# atmega2560.net
KiCad netlist of a schematic drawn in EAGLE
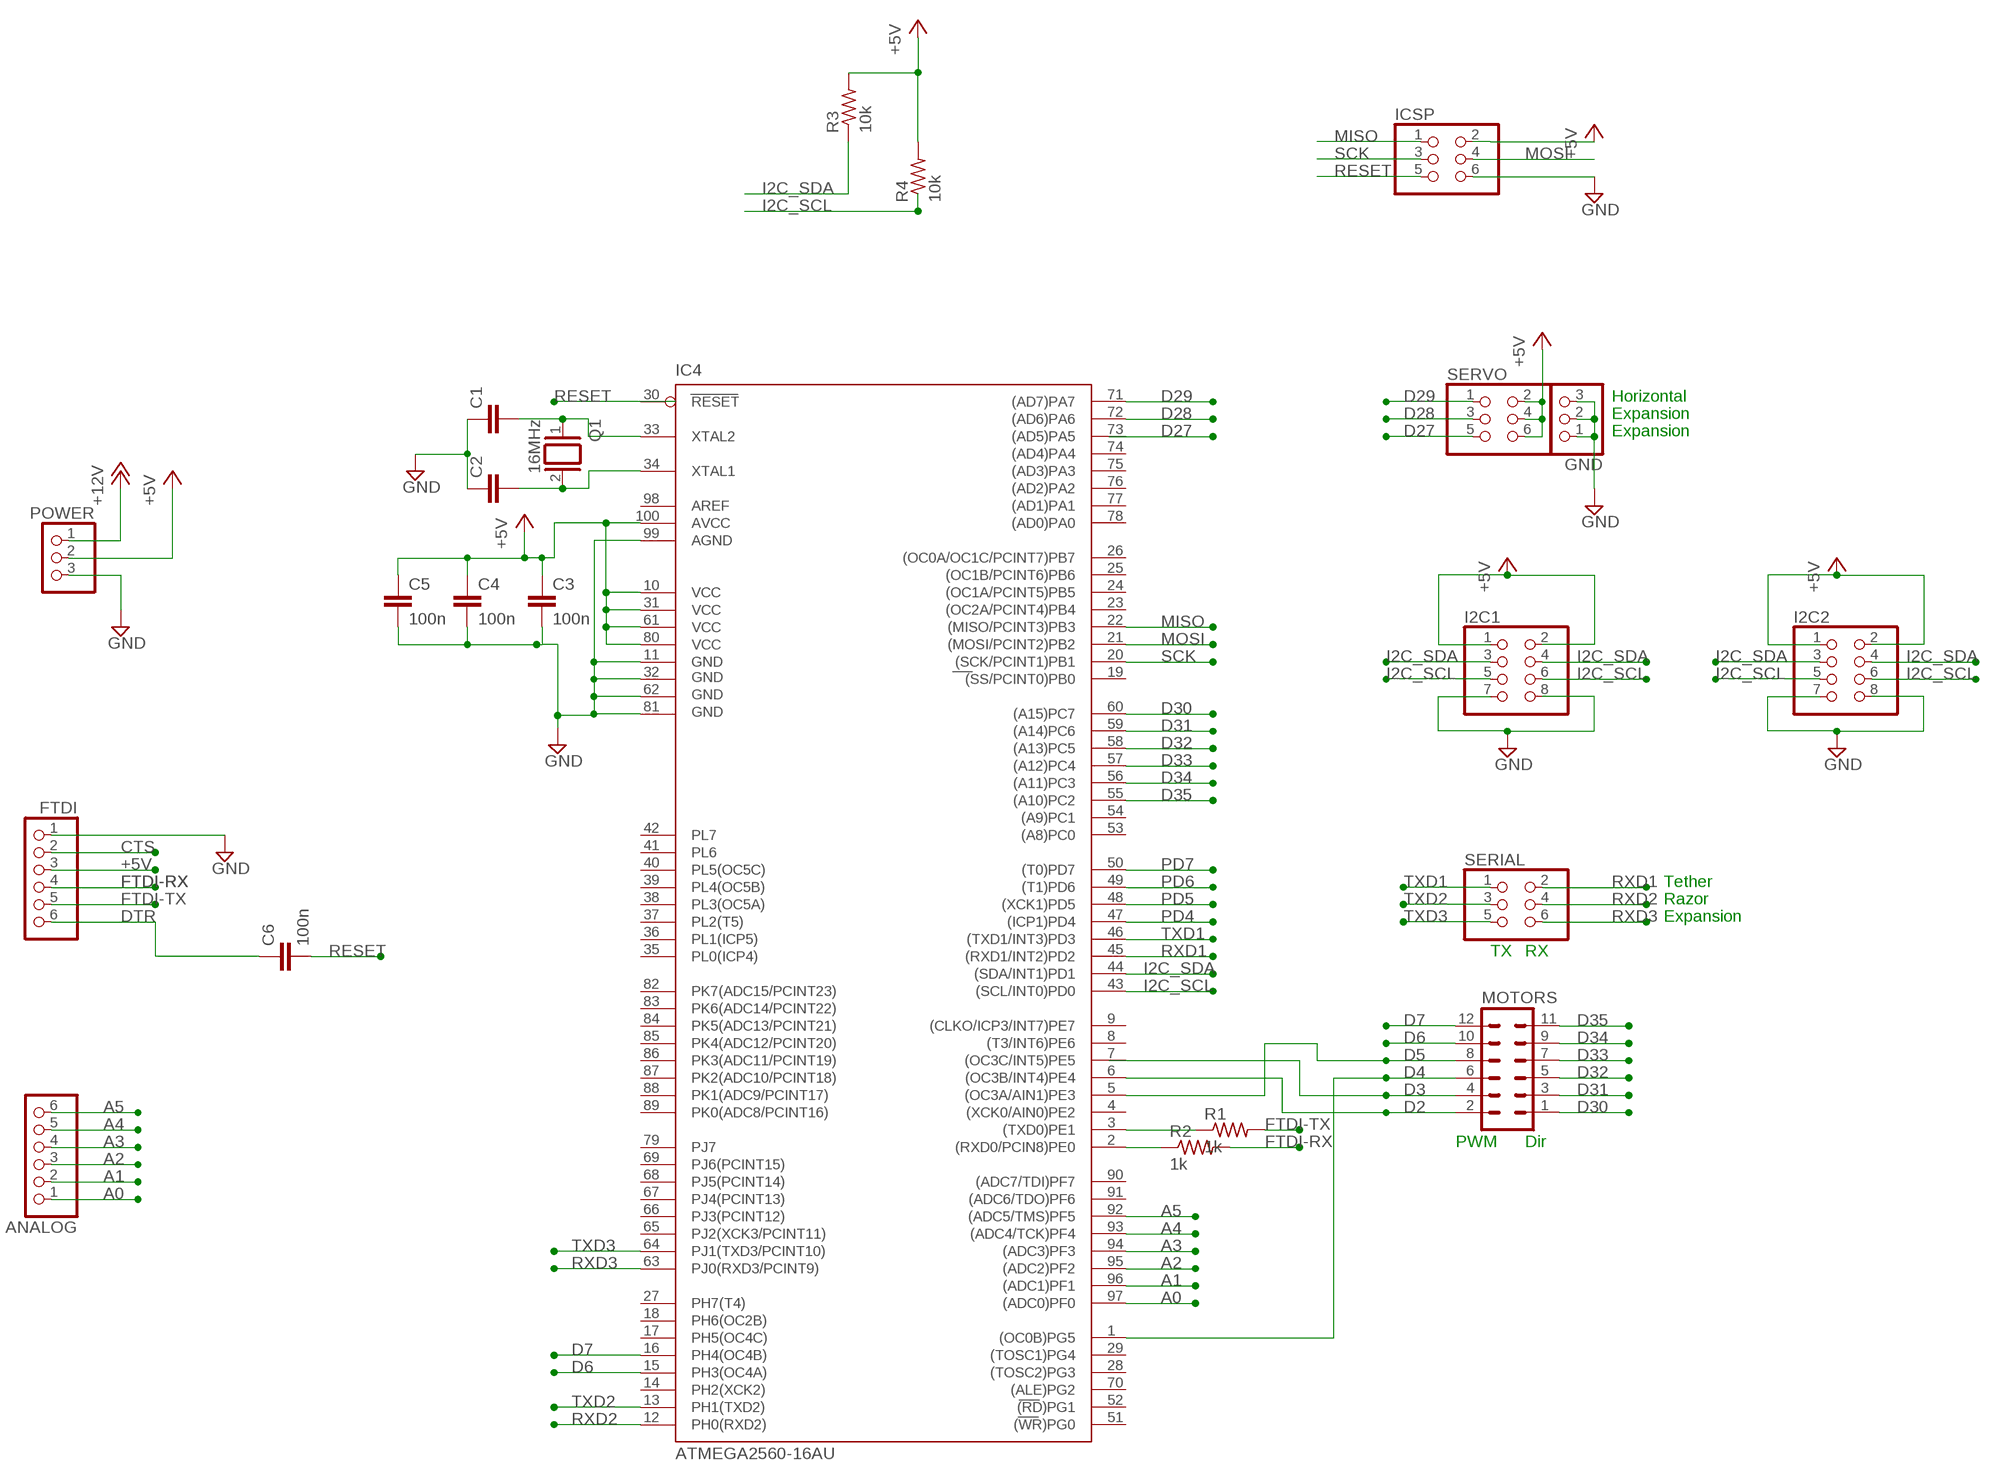
[diagram p0: schematic, sheet 1]

(export (version "E")
  (design (tool "Eeschema 10.0.6"))
  (components
    (comp (ref "ANALOG")
      (value "PINHD-1X6")
      (footprint "eagle-import:1X06")
      (libsource (lib "eagle-import") (part "PINHD-1X6"))
    )
    (comp (ref "C1")
      (value "C5/3.5")
      (footprint "eagle-import:C5B3.5")
      (libsource (lib "eagle-import") (part "C5/3.5"))
    )
    (comp (ref "C2")
      (value "C5/3.5")
      (footprint "eagle-import:C5B3.5")
      (libsource (lib "eagle-import") (part "C5/3.5"))
    )
    (comp (ref "C3")
      (value "100n")
      (footprint "eagle-import:C5B3.5")
      (libsource (lib "eagle-import") (part "C5/3.5"))
    )
    (comp (ref "C4")
      (value "100n")
      (footprint "eagle-import:C5B3.5")
      (libsource (lib "eagle-import") (part "C5/3.5"))
    )
    (comp (ref "C5")
      (value "100n")
      (footprint "eagle-import:C5B3.5")
      (libsource (lib "eagle-import") (part "C5/3.5"))
    )
    (comp (ref "C6")
      (value "100n")
      (footprint "eagle-import:C050-030X075")
      (libsource (lib "eagle-import") (part "C-EU050-030X075"))
    )
    (comp (ref "FTDI")
      (value "PINHD-1X6")
      (footprint "eagle-import:1X06")
      (libsource (lib "eagle-import") (part "PINHD-1X6"))
    )
    (comp (ref "GND")
      (value "PINHD-1X3")
      (footprint "eagle-import:1X03")
      (libsource (lib "eagle-import") (part "PINHD-1X3"))
    )
    (comp (ref "I2C1")
      (value "PINHD-2X4")
      (footprint "eagle-import:2X04")
      (libsource (lib "eagle-import") (part "PINHD-2X4"))
    )
    (comp (ref "I2C2")
      (value "PINHD-2X4")
      (footprint "eagle-import:2X04")
      (libsource (lib "eagle-import") (part "PINHD-2X4"))
    )
    (comp (ref "IC4")
      (value "ATMEGA2560-16AU")
      (footprint "eagle-import:TQFP100")
      (libsource (lib "eagle-import") (part "ATMEGAAU2560-16"))
    )
    (comp (ref "ICSP")
      (value "PINHD-2X3")
      (footprint "eagle-import:2X03")
      (libsource (lib "eagle-import") (part "PINHD-2X3"))
    )
    (comp (ref "MOTORS")
      (value "MA06-2")
      (footprint "eagle-import:MA06-2")
      (libsource (lib "eagle-import") (part "MA06-2"))
    )
    (comp (ref "POWER")
      (value "PINHD-1X3")
      (footprint "eagle-import:1X03")
      (libsource (lib "eagle-import") (part "PINHD-1X3"))
    )
    (comp (ref "Q1")
      (value "16MHz")
      (footprint "eagle-import:QS")
      (libsource (lib "eagle-import") (part "XTAL/S"))
    )
    (comp (ref "R1")
      (value "1k")
      (footprint "eagle-import:0207_7")
      (libsource (lib "eagle-import") (part "R-US_0207/7"))
    )
    (comp (ref "R2")
      (value "1k")
      (footprint "eagle-import:0207_7")
      (libsource (lib "eagle-import") (part "R-US_0207/7"))
    )
    (comp (ref "R3")
      (value "10k")
      (footprint "eagle-import:0207_7")
      (libsource (lib "eagle-import") (part "R-US_0207/7"))
    )
    (comp (ref "R4")
      (value "10k")
      (footprint "eagle-import:0207_7")
      (libsource (lib "eagle-import") (part "R-US_0207/7"))
    )
    (comp (ref "SERIAL")
      (value "PINHD-2X3")
      (footprint "eagle-import:2X03")
      (libsource (lib "eagle-import") (part "PINHD-2X3"))
    )
    (comp (ref "SERVO")
      (value "PINHD-2X3")
      (footprint "eagle-import:2X03")
      (libsource (lib "eagle-import") (part "PINHD-2X3"))
    )
  )
  (nets
    (net (code "1") (name "+5V") (class "Default")
      (node (ref "C3") (pin "1") (pinfunction "1_1") (pintype "passive"))
      (node (ref "C4") (pin "1") (pinfunction "1_1") (pintype "passive"))
      (node (ref "C5") (pin "1") (pinfunction "1_1") (pintype "passive"))
      (node (ref "FTDI") (pin "3") (pinfunction "3_3") (pintype "passive"))
      (node (ref "I2C1") (pin "1") (pinfunction "1_1") (pintype "passive"))
      (node (ref "I2C1") (pin "2") (pinfunction "2_2") (pintype "passive"))
      (node (ref "I2C2") (pin "1") (pinfunction "1_1") (pintype "passive"))
      (node (ref "I2C2") (pin "2") (pinfunction "2_2") (pintype "passive"))
      (node (ref "IC4") (pin "10") (pinfunction "VCC_10") (pintype "power_in"))
      (node (ref "IC4") (pin "100") (pinfunction "AVCC_100") (pintype "power_in"))
      (node (ref "IC4") (pin "31") (pinfunction "VCC1_31") (pintype "power_in"))
      (node (ref "IC4") (pin "61") (pinfunction "VCC2_61") (pintype "power_in"))
      (node (ref "IC4") (pin "80") (pinfunction "VCC3_80") (pintype "power_in"))
      (node (ref "ICSP") (pin "2") (pinfunction "2_2") (pintype "passive"))
      (node (ref "POWER") (pin "2") (pinfunction "2_2") (pintype "passive"))
      (node (ref "R3") (pin "2") (pinfunction "2_2") (pintype "passive"))
      (node (ref "R4") (pin "2") (pinfunction "2_2") (pintype "passive"))
      (node (ref "SERVO") (pin "2") (pinfunction "2_2") (pintype "passive"))
      (node (ref "SERVO") (pin "4") (pinfunction "4_4") (pintype "passive"))
      (node (ref "SERVO") (pin "6") (pinfunction "6_6") (pintype "passive"))
    )
    (net (code "2") (name "+12V") (class "Default")
      (node (ref "POWER") (pin "1") (pinfunction "1_1") (pintype "passive"))
    )
    (net (code "3") (name "/A0") (class "Default")
      (node (ref "ANALOG") (pin "1") (pinfunction "1_1") (pintype "passive"))
      (node (ref "IC4") (pin "97") (pinfunction "(ADC0)PF0_97") (pintype "bidirectional"))
    )
    (net (code "4") (name "/A1") (class "Default")
      (node (ref "ANALOG") (pin "2") (pinfunction "2_2") (pintype "passive"))
      (node (ref "IC4") (pin "96") (pinfunction "(ADC1)PF1_96") (pintype "bidirectional"))
    )
    (net (code "5") (name "/A2") (class "Default")
      (node (ref "ANALOG") (pin "3") (pinfunction "3_3") (pintype "passive"))
      (node (ref "IC4") (pin "95") (pinfunction "(ADC2)PF2_95") (pintype "bidirectional"))
    )
    (net (code "6") (name "/A3") (class "Default")
      (node (ref "ANALOG") (pin "4") (pinfunction "4_4") (pintype "passive"))
      (node (ref "IC4") (pin "94") (pinfunction "(ADC3)PF3_94") (pintype "bidirectional"))
    )
    (net (code "7") (name "/A4") (class "Default")
      (node (ref "ANALOG") (pin "5") (pinfunction "5_5") (pintype "passive"))
      (node (ref "IC4") (pin "93") (pinfunction "(ADC4/TCK)PF4_93") (pintype "bidirectional"))
    )
    (net (code "8") (name "/A5") (class "Default")
      (node (ref "ANALOG") (pin "6") (pinfunction "6_6") (pintype "passive"))
      (node (ref "IC4") (pin "92") (pinfunction "(ADC5/TMS)PF5_92") (pintype "bidirectional"))
    )
    (net (code "9") (name "/CTS") (class "Default")
      (node (ref "FTDI") (pin "2") (pinfunction "2_2") (pintype "passive"))
    )
    (net (code "10") (name "/D2") (class "Default")
      (node (ref "IC4") (pin "6") (pinfunction "(OC3B/INT4)PE4_6") (pintype "bidirectional"))
      (node (ref "MOTORS") (pin "2") (pinfunction "2_2") (pintype "passive"))
    )
    (net (code "11") (name "/D3") (class "Default")
      (node (ref "MOTORS") (pin "4") (pinfunction "4_4") (pintype "passive"))
    )
    (net (code "12") (name "/D4") (class "Default")
      (node (ref "IC4") (pin "1") (pinfunction "(OC0B)PG5_1") (pintype "bidirectional"))
      (node (ref "MOTORS") (pin "6") (pinfunction "6_6") (pintype "passive"))
    )
    (net (code "13") (name "/D5") (class "Default")
      (node (ref "IC4") (pin "5") (pinfunction "(OC3A/AIN1)PE3_5") (pintype "bidirectional"))
      (node (ref "MOTORS") (pin "8") (pinfunction "8_8") (pintype "passive"))
    )
    (net (code "14") (name "/D6") (class "Default")
      (node (ref "IC4") (pin "15") (pinfunction "PH3(OC4A)_15") (pintype "bidirectional"))
      (node (ref "MOTORS") (pin "10") (pinfunction "10_10") (pintype "passive"))
    )
    (net (code "15") (name "/D7") (class "Default")
      (node (ref "IC4") (pin "16") (pinfunction "PH4(OC4B)_16") (pintype "bidirectional"))
      (node (ref "MOTORS") (pin "12") (pinfunction "12_12") (pintype "passive"))
    )
    (net (code "16") (name "/D27") (class "Default")
      (node (ref "SERVO") (pin "5") (pinfunction "5_5") (pintype "passive"))
    )
    (net (code "17") (name "/D28") (class "Default")
      (node (ref "IC4") (pin "72") (pinfunction "(AD6)PA6_72") (pintype "bidirectional"))
      (node (ref "SERVO") (pin "3") (pinfunction "3_3") (pintype "passive"))
    )
    (net (code "18") (name "/D29") (class "Default")
      (node (ref "IC4") (pin "71") (pinfunction "(AD7)PA7_71") (pintype "bidirectional"))
      (node (ref "SERVO") (pin "1") (pinfunction "1_1") (pintype "passive"))
    )
    (net (code "19") (name "/D30") (class "Default")
      (node (ref "IC4") (pin "60") (pinfunction "(A15)PC7_60") (pintype "bidirectional"))
      (node (ref "MOTORS") (pin "1") (pinfunction "1_1") (pintype "passive"))
    )
    (net (code "20") (name "/D31") (class "Default")
      (node (ref "IC4") (pin "59") (pinfunction "(A14)PC6_59") (pintype "bidirectional"))
      (node (ref "MOTORS") (pin "3") (pinfunction "3_3") (pintype "passive"))
    )
    (net (code "21") (name "/D32") (class "Default")
      (node (ref "IC4") (pin "58") (pinfunction "(A13)PC5_58") (pintype "bidirectional"))
      (node (ref "MOTORS") (pin "5") (pinfunction "5_5") (pintype "passive"))
    )
    (net (code "22") (name "/D33") (class "Default")
      (node (ref "IC4") (pin "57") (pinfunction "(A12)PC4_57") (pintype "bidirectional"))
      (node (ref "MOTORS") (pin "7") (pinfunction "7_7") (pintype "passive"))
    )
    (net (code "23") (name "/D34") (class "Default")
      (node (ref "IC4") (pin "56") (pinfunction "(A11)PC3_56") (pintype "bidirectional"))
      (node (ref "MOTORS") (pin "9") (pinfunction "9_9") (pintype "passive"))
    )
    (net (code "24") (name "/D35") (class "Default")
      (node (ref "IC4") (pin "55") (pinfunction "(A10)PC2_55") (pintype "bidirectional"))
      (node (ref "MOTORS") (pin "11") (pinfunction "11_11") (pintype "passive"))
    )
    (net (code "25") (name "/DTR") (class "Default")
      (node (ref "C6") (pin "1") (pinfunction "1_1") (pintype "passive"))
      (node (ref "FTDI") (pin "6") (pinfunction "6_6") (pintype "passive"))
    )
    (net (code "26") (name "/FTDI-RX") (class "Default")
      (node (ref "FTDI") (pin "4") (pinfunction "4_4") (pintype "passive"))
      (node (ref "R2") (pin "2") (pinfunction "2_2") (pintype "passive"))
    )
    (net (code "27") (name "/FTDI-TX") (class "Default")
      (node (ref "FTDI") (pin "5") (pinfunction "5_5") (pintype "passive"))
      (node (ref "R1") (pin "2") (pinfunction "2_2") (pintype "passive"))
    )
    (net (code "28") (name "/I2C_SCL") (class "Default")
      (node (ref "I2C1") (pin "5") (pinfunction "5_5") (pintype "passive"))
      (node (ref "I2C1") (pin "6") (pinfunction "6_6") (pintype "passive"))
      (node (ref "I2C2") (pin "5") (pinfunction "5_5") (pintype "passive"))
      (node (ref "I2C2") (pin "6") (pinfunction "6_6") (pintype "passive"))
      (node (ref "IC4") (pin "43") (pinfunction "(SCL/INT0)PD0_43") (pintype "bidirectional"))
      (node (ref "R4") (pin "1") (pinfunction "1_1") (pintype "passive"))
    )
    (net (code "29") (name "/I2C_SDA") (class "Default")
      (node (ref "I2C1") (pin "3") (pinfunction "3_3") (pintype "passive"))
      (node (ref "I2C1") (pin "4") (pinfunction "4_4") (pintype "passive"))
      (node (ref "I2C2") (pin "3") (pinfunction "3_3") (pintype "passive"))
      (node (ref "I2C2") (pin "4") (pinfunction "4_4") (pintype "passive"))
      (node (ref "IC4") (pin "44") (pinfunction "(SDA/INT1)PD1_44") (pintype "bidirectional"))
      (node (ref "R3") (pin "1") (pinfunction "1_1") (pintype "passive"))
    )
    (net (code "30") (name "/MISO") (class "Default")
      (node (ref "IC4") (pin "22") (pinfunction "(MISO/PCINT3)PB3_22") (pintype "bidirectional"))
      (node (ref "ICSP") (pin "1") (pinfunction "1_1") (pintype "passive"))
    )
    (net (code "31") (name "/MOSI") (class "Default")
      (node (ref "IC4") (pin "21") (pinfunction "(MOSI/PCINT2)PB2_21") (pintype "bidirectional"))
      (node (ref "ICSP") (pin "4") (pinfunction "4_4") (pintype "passive"))
    )
    (net (code "32") (name "/PD4") (class "Default")
      (node (ref "IC4") (pin "47") (pinfunction "(ICP1)PD4_47") (pintype "bidirectional"))
    )
    (net (code "33") (name "/PD5") (class "Default")
      (node (ref "IC4") (pin "48") (pinfunction "(XCK1)PD5_48") (pintype "bidirectional"))
    )
    (net (code "34") (name "/PD6") (class "Default")
      (node (ref "IC4") (pin "49") (pinfunction "(T1)PD6_49") (pintype "bidirectional"))
    )
    (net (code "35") (name "/PD7") (class "Default")
      (node (ref "IC4") (pin "50") (pinfunction "(T0)PD7_50") (pintype "bidirectional"))
    )
    (net (code "36") (name "/RESET") (class "Default")
      (node (ref "C6") (pin "2") (pinfunction "2_2") (pintype "passive"))
      (node (ref "ICSP") (pin "5") (pinfunction "5_5") (pintype "passive"))
    )
    (net (code "37") (name "/RXD1") (class "Default")
      (node (ref "IC4") (pin "45") (pinfunction "(RXD1/INT2)PD2_45") (pintype "bidirectional"))
      (node (ref "SERIAL") (pin "2") (pinfunction "2_2") (pintype "passive"))
    )
    (net (code "38") (name "/RXD2") (class "Default")
      (node (ref "IC4") (pin "12") (pinfunction "PH0(RXD2)_12") (pintype "bidirectional"))
      (node (ref "SERIAL") (pin "4") (pinfunction "4_4") (pintype "passive"))
    )
    (net (code "39") (name "/RXD3") (class "Default")
      (node (ref "IC4") (pin "63") (pinfunction "PJ0(RXD3/PCINT9)_63") (pintype "bidirectional"))
      (node (ref "SERIAL") (pin "6") (pinfunction "6_6") (pintype "passive"))
    )
    (net (code "40") (name "/SCK") (class "Default")
      (node (ref "IC4") (pin "20") (pinfunction "(SCK/PCINT1)PB1_20") (pintype "bidirectional"))
      (node (ref "ICSP") (pin "3") (pinfunction "3_3") (pintype "passive"))
    )
    (net (code "41") (name "/TXD1") (class "Default")
      (node (ref "IC4") (pin "46") (pinfunction "(TXD1/INT3)PD3_46") (pintype "bidirectional"))
      (node (ref "SERIAL") (pin "1") (pinfunction "1_1") (pintype "passive"))
    )
    (net (code "42") (name "/TXD2") (class "Default")
      (node (ref "IC4") (pin "13") (pinfunction "PH1(TXD2)_13") (pintype "bidirectional"))
      (node (ref "SERIAL") (pin "3") (pinfunction "3_3") (pintype "passive"))
    )
    (net (code "43") (name "/TXD3") (class "Default")
      (node (ref "IC4") (pin "64") (pinfunction "PJ1(TXD3/PCINT10)_64") (pintype "bidirectional"))
      (node (ref "SERIAL") (pin "5") (pinfunction "5_5") (pintype "passive"))
    )
    (net (code "44") (name "GND") (class "Default")
      (node (ref "C1") (pin "1") (pinfunction "1_1") (pintype "passive"))
      (node (ref "C2") (pin "1") (pinfunction "1_1") (pintype "passive"))
      (node (ref "C3") (pin "2") (pinfunction "2_2") (pintype "passive"))
      (node (ref "C4") (pin "2") (pinfunction "2_2") (pintype "passive"))
      (node (ref "C5") (pin "2") (pinfunction "2_2") (pintype "passive"))
      (node (ref "FTDI") (pin "1") (pinfunction "1_1") (pintype "passive"))
      (node (ref "GND") (pin "1") (pinfunction "1_1") (pintype "passive"))
      (node (ref "GND") (pin "2") (pinfunction "2_2") (pintype "passive"))
      (node (ref "GND") (pin "3") (pinfunction "3_3") (pintype "passive"))
      (node (ref "I2C1") (pin "7") (pinfunction "7_7") (pintype "passive"))
      (node (ref "I2C1") (pin "8") (pinfunction "8_8") (pintype "passive"))
      (node (ref "I2C2") (pin "7") (pinfunction "7_7") (pintype "passive"))
      (node (ref "I2C2") (pin "8") (pinfunction "8_8") (pintype "passive"))
      (node (ref "IC4") (pin "11") (pinfunction "GND_11") (pintype "power_in"))
      (node (ref "IC4") (pin "32") (pinfunction "GND1_32") (pintype "power_in"))
      (node (ref "IC4") (pin "62") (pinfunction "GND2_62") (pintype "power_in"))
      (node (ref "IC4") (pin "81") (pinfunction "GND3_81") (pintype "power_in"))
      (node (ref "IC4") (pin "99") (pinfunction "AGND_99") (pintype "power_in"))
      (node (ref "ICSP") (pin "6") (pinfunction "6_6") (pintype "passive"))
      (node (ref "POWER") (pin "3") (pinfunction "3_3") (pintype "passive"))
    )
    (net (code "45") (name "Net-(IC4-(RXD0{slash}PCIN8)PE0)") (class "Default")
      (node (ref "IC4") (pin "2") (pinfunction "(RXD0/PCIN8)PE0_2") (pintype "bidirectional"))
      (node (ref "R2") (pin "1") (pinfunction "1_1") (pintype "passive"))
    )
    (net (code "46") (name "Net-(IC4-(TXD0)PE1)") (class "Default")
      (node (ref "IC4") (pin "3") (pinfunction "(TXD0)PE1_3") (pintype "bidirectional"))
      (node (ref "R1") (pin "1") (pinfunction "1_1") (pintype "passive"))
    )
    (net (code "47") (name "Net-(IC4-XTAL1)") (class "Default")
      (node (ref "C2") (pin "2") (pinfunction "2_2") (pintype "passive"))
      (node (ref "IC4") (pin "34") (pinfunction "XTAL1_34") (pintype "input"))
      (node (ref "Q1") (pin "2") (pinfunction "2_2") (pintype "passive"))
    )
    (net (code "48") (name "Net-(IC4-XTAL2)") (class "Default")
      (node (ref "C1") (pin "2") (pinfunction "2_2") (pintype "passive"))
      (node (ref "IC4") (pin "33") (pinfunction "XTAL2_33") (pintype "output"))
      (node (ref "Q1") (pin "1") (pinfunction "1_1") (pintype "passive"))
    )
    (net (code "49") (name "unconnected-(IC4-(A8)PC0-Pad53)") (class "Default")
      (node (ref "IC4") (pin "53") (pinfunction "(A8)PC0_53") (pintype "bidirectional"))
    )
    (net (code "50") (name "unconnected-(IC4-(A9)PC1-Pad54)") (class "Default")
      (node (ref "IC4") (pin "54") (pinfunction "(A9)PC1_54") (pintype "bidirectional"))
    )
    (net (code "51") (name "unconnected-(IC4-(AD0)PA0-Pad78)") (class "Default")
      (node (ref "IC4") (pin "78") (pinfunction "(AD0)PA0_78") (pintype "bidirectional"))
    )
    (net (code "52") (name "unconnected-(IC4-(AD1)PA1-Pad77)") (class "Default")
      (node (ref "IC4") (pin "77") (pinfunction "(AD1)PA1_77") (pintype "bidirectional"))
    )
    (net (code "53") (name "unconnected-(IC4-(AD2)PA2-Pad76)") (class "Default")
      (node (ref "IC4") (pin "76") (pinfunction "(AD2)PA2_76") (pintype "bidirectional"))
    )
    (net (code "54") (name "unconnected-(IC4-(AD3)PA3-Pad75)") (class "Default")
      (node (ref "IC4") (pin "75") (pinfunction "(AD3)PA3_75") (pintype "bidirectional"))
    )
    (net (code "55") (name "unconnected-(IC4-(AD4)PA4-Pad74)") (class "Default")
      (node (ref "IC4") (pin "74") (pinfunction "(AD4)PA4_74") (pintype "bidirectional"))
    )
    (net (code "56") (name "unconnected-(IC4-(AD5)PA5-Pad73)") (class "Default")
      (node (ref "IC4") (pin "73") (pinfunction "(AD5)PA5_73") (pintype "bidirectional"))
    )
    (net (code "57") (name "unconnected-(IC4-(ADC6{slash}TDO)PF6-Pad91)") (class "Default")
      (node (ref "IC4") (pin "91") (pinfunction "(ADC6/TDO)PF6_91") (pintype "bidirectional"))
    )
    (net (code "58") (name "unconnected-(IC4-(ADC7{slash}TDI)PF7-Pad90)") (class "Default")
      (node (ref "IC4") (pin "90") (pinfunction "(ADC7/TDI)PF7_90") (pintype "bidirectional"))
    )
    (net (code "59") (name "unconnected-(IC4-(ALE)PG2-Pad70)") (class "Default")
      (node (ref "IC4") (pin "70") (pinfunction "(ALE)PG2_70") (pintype "bidirectional"))
    )
    (net (code "60") (name "unconnected-(IC4-(CLKO{slash}ICP3{slash}INT7)PE7-Pad9)") (class "Default")
      (node (ref "IC4") (pin "9") (pinfunction "(CLKO/ICP3/INT7)PE7_9") (pintype "bidirectional"))
    )
    (net (code "61") (name "unconnected-(IC4-(OC0A{slash}OC1C{slash}PCINT7)PB7-Pad26)") (class "Default")
      (node (ref "IC4") (pin "26") (pinfunction "(OC0A/OC1C/PCINT7)PB7_26") (pintype "bidirectional"))
    )
    (net (code "62") (name "unconnected-(IC4-(OC1A{slash}PCINT5)PB5-Pad24)") (class "Default")
      (node (ref "IC4") (pin "24") (pinfunction "(OC1A/PCINT5)PB5_24") (pintype "bidirectional"))
    )
    (net (code "63") (name "unconnected-(IC4-(OC1B{slash}PCINT6)PB6-Pad25)") (class "Default")
      (node (ref "IC4") (pin "25") (pinfunction "(OC1B/PCINT6)PB6_25") (pintype "bidirectional"))
    )
    (net (code "64") (name "unconnected-(IC4-(OC2A{slash}PCINT4)PB4-Pad23)") (class "Default")
      (node (ref "IC4") (pin "23") (pinfunction "(OC2A/PCINT4)PB4_23") (pintype "bidirectional"))
    )
    (net (code "65") (name "unconnected-(IC4-(OC3C{slash}INT5)PE5-Pad7)") (class "Default")
      (node (ref "IC4") (pin "7") (pinfunction "(OC3C/INT5)PE5_7") (pintype "bidirectional"))
    )
    (net (code "66") (name "unconnected-(IC4-(RD)PG1-Pad52)") (class "Default")
      (node (ref "IC4") (pin "52") (pinfunction "(RD)PG1_52") (pintype "bidirectional"))
    )
    (net (code "67") (name "unconnected-(IC4-(SS{slash}PCINT0)PB0-Pad19)") (class "Default")
      (node (ref "IC4") (pin "19") (pinfunction "(SS/PCINT0)PB0_19") (pintype "bidirectional"))
    )
    (net (code "68") (name "unconnected-(IC4-(T3{slash}INT6)PE6-Pad8)") (class "Default")
      (node (ref "IC4") (pin "8") (pinfunction "(T3/INT6)PE6_8") (pintype "bidirectional"))
    )
    (net (code "69") (name "unconnected-(IC4-(TOSC1)PG4-Pad29)") (class "Default")
      (node (ref "IC4") (pin "29") (pinfunction "(TOSC1)PG4_29") (pintype "bidirectional"))
    )
    (net (code "70") (name "unconnected-(IC4-(TOSC2)PG3-Pad28)") (class "Default")
      (node (ref "IC4") (pin "28") (pinfunction "(TOSC2)PG3_28") (pintype "bidirectional"))
    )
    (net (code "71") (name "unconnected-(IC4-(WR)PG0-Pad51)") (class "Default")
      (node (ref "IC4") (pin "51") (pinfunction "(WR)PG0_51") (pintype "bidirectional"))
    )
    (net (code "72") (name "unconnected-(IC4-(XCK0{slash}AIN0)PE2-Pad4)") (class "Default")
      (node (ref "IC4") (pin "4") (pinfunction "(XCK0/AIN0)PE2_4") (pintype "bidirectional"))
    )
    (net (code "73") (name "unconnected-(IC4-AREF-Pad98)") (class "Default")
      (node (ref "IC4") (pin "98") (pinfunction "AREF_98") (pintype "bidirectional"))
    )
    (net (code "74") (name "unconnected-(IC4-PH2(XCK2)-Pad14)") (class "Default")
      (node (ref "IC4") (pin "14") (pinfunction "PH2(XCK2)_14") (pintype "bidirectional"))
    )
    (net (code "75") (name "unconnected-(IC4-PH5(OC4C)-Pad17)") (class "Default")
      (node (ref "IC4") (pin "17") (pinfunction "PH5(OC4C)_17") (pintype "bidirectional"))
    )
    (net (code "76") (name "unconnected-(IC4-PH6(OC2B)-Pad18)") (class "Default")
      (node (ref "IC4") (pin "18") (pinfunction "PH6(OC2B)_18") (pintype "bidirectional"))
    )
    (net (code "77") (name "unconnected-(IC4-PH7(T4)-Pad27)") (class "Default")
      (node (ref "IC4") (pin "27") (pinfunction "PH7(T4)_27") (pintype "bidirectional"))
    )
    (net (code "78") (name "unconnected-(IC4-PJ2(XCK3{slash}PCINT11)-Pad65)") (class "Default")
      (node (ref "IC4") (pin "65") (pinfunction "PJ2(XCK3/PCINT11)_65") (pintype "bidirectional"))
    )
    (net (code "79") (name "unconnected-(IC4-PJ3(PCINT12)-Pad66)") (class "Default")
      (node (ref "IC4") (pin "66") (pinfunction "PJ3(PCINT12)_66") (pintype "bidirectional"))
    )
    (net (code "80") (name "unconnected-(IC4-PJ4(PCINT13)-Pad67)") (class "Default")
      (node (ref "IC4") (pin "67") (pinfunction "PJ4(PCINT13)_67") (pintype "bidirectional"))
    )
    (net (code "81") (name "unconnected-(IC4-PJ5(PCINT14)-Pad68)") (class "Default")
      (node (ref "IC4") (pin "68") (pinfunction "PJ5(PCINT14)_68") (pintype "bidirectional"))
    )
    (net (code "82") (name "unconnected-(IC4-PJ6(PCINT15)-Pad69)") (class "Default")
      (node (ref "IC4") (pin "69") (pinfunction "PJ6(PCINT15)_69") (pintype "bidirectional"))
    )
    (net (code "83") (name "unconnected-(IC4-PJ7-Pad79)") (class "Default")
      (node (ref "IC4") (pin "79") (pinfunction "PJ7_79") (pintype "bidirectional"))
    )
    (net (code "84") (name "unconnected-(IC4-PK0(ADC8{slash}PCINT16)-Pad89)") (class "Default")
      (node (ref "IC4") (pin "89") (pinfunction "PK0(ADC8/PCINT16)_89") (pintype "bidirectional"))
    )
    (net (code "85") (name "unconnected-(IC4-PK1(ADC9{slash}PCINT17)-Pad88)") (class "Default")
      (node (ref "IC4") (pin "88") (pinfunction "PK1(ADC9/PCINT17)_88") (pintype "bidirectional"))
    )
    (net (code "86") (name "unconnected-(IC4-PK2(ADC10{slash}PCINT18)-Pad87)") (class "Default")
      (node (ref "IC4") (pin "87") (pinfunction "PK2(ADC10/PCINT18)_87") (pintype "bidirectional"))
    )
    (net (code "87") (name "unconnected-(IC4-PK3(ADC11{slash}PCINT19)-Pad86)") (class "Default")
      (node (ref "IC4") (pin "86") (pinfunction "PK3(ADC11/PCINT19)_86") (pintype "bidirectional"))
    )
    (net (code "88") (name "unconnected-(IC4-PK4(ADC12{slash}PCINT20)-Pad85)") (class "Default")
      (node (ref "IC4") (pin "85") (pinfunction "PK4(ADC12/PCINT20)_85") (pintype "bidirectional"))
    )
    (net (code "89") (name "unconnected-(IC4-PK5(ADC13{slash}PCINT21)-Pad84)") (class "Default")
      (node (ref "IC4") (pin "84") (pinfunction "PK5(ADC13/PCINT21)_84") (pintype "bidirectional"))
    )
    (net (code "90") (name "unconnected-(IC4-PK6(ADC14{slash}PCINT22)-Pad83)") (class "Default")
      (node (ref "IC4") (pin "83") (pinfunction "PK6(ADC14/PCINT22)_83") (pintype "bidirectional"))
    )
    (net (code "91") (name "unconnected-(IC4-PK7(ADC15{slash}PCINT23)-Pad82)") (class "Default")
      (node (ref "IC4") (pin "82") (pinfunction "PK7(ADC15/PCINT23)_82") (pintype "bidirectional"))
    )
    (net (code "92") (name "unconnected-(IC4-PL0(ICP4)-Pad35)") (class "Default")
      (node (ref "IC4") (pin "35") (pinfunction "PL0(ICP4)_35") (pintype "bidirectional"))
    )
    (net (code "93") (name "unconnected-(IC4-PL1(ICP5)-Pad36)") (class "Default")
      (node (ref "IC4") (pin "36") (pinfunction "PL1(ICP5)_36") (pintype "bidirectional"))
    )
    (net (code "94") (name "unconnected-(IC4-PL2(T5)-Pad37)") (class "Default")
      (node (ref "IC4") (pin "37") (pinfunction "PL2(T5)_37") (pintype "bidirectional"))
    )
    (net (code "95") (name "unconnected-(IC4-PL3(OC5A)-Pad38)") (class "Default")
      (node (ref "IC4") (pin "38") (pinfunction "PL3(OC5A)_38") (pintype "bidirectional"))
    )
    (net (code "96") (name "unconnected-(IC4-PL4(OC5B)-Pad39)") (class "Default")
      (node (ref "IC4") (pin "39") (pinfunction "PL4(OC5B)_39") (pintype "bidirectional"))
    )
    (net (code "97") (name "unconnected-(IC4-PL5(OC5C)-Pad40)") (class "Default")
      (node (ref "IC4") (pin "40") (pinfunction "PL5(OC5C)_40") (pintype "bidirectional"))
    )
    (net (code "98") (name "unconnected-(IC4-PL6-Pad41)") (class "Default")
      (node (ref "IC4") (pin "41") (pinfunction "PL6_41") (pintype "bidirectional"))
    )
    (net (code "99") (name "unconnected-(IC4-PL7-Pad42)") (class "Default")
      (node (ref "IC4") (pin "42") (pinfunction "PL7_42") (pintype "bidirectional"))
    )
    (net (code "100") (name "unconnected-(IC4-RESET-Pad30)") (class "Default")
      (node (ref "IC4") (pin "30") (pinfunction "RESET_30") (pintype "input"))
    )
  )
)
